# SJ2096POE_USB.net
KiCad netlist of a schematic drawn in Altium Designer
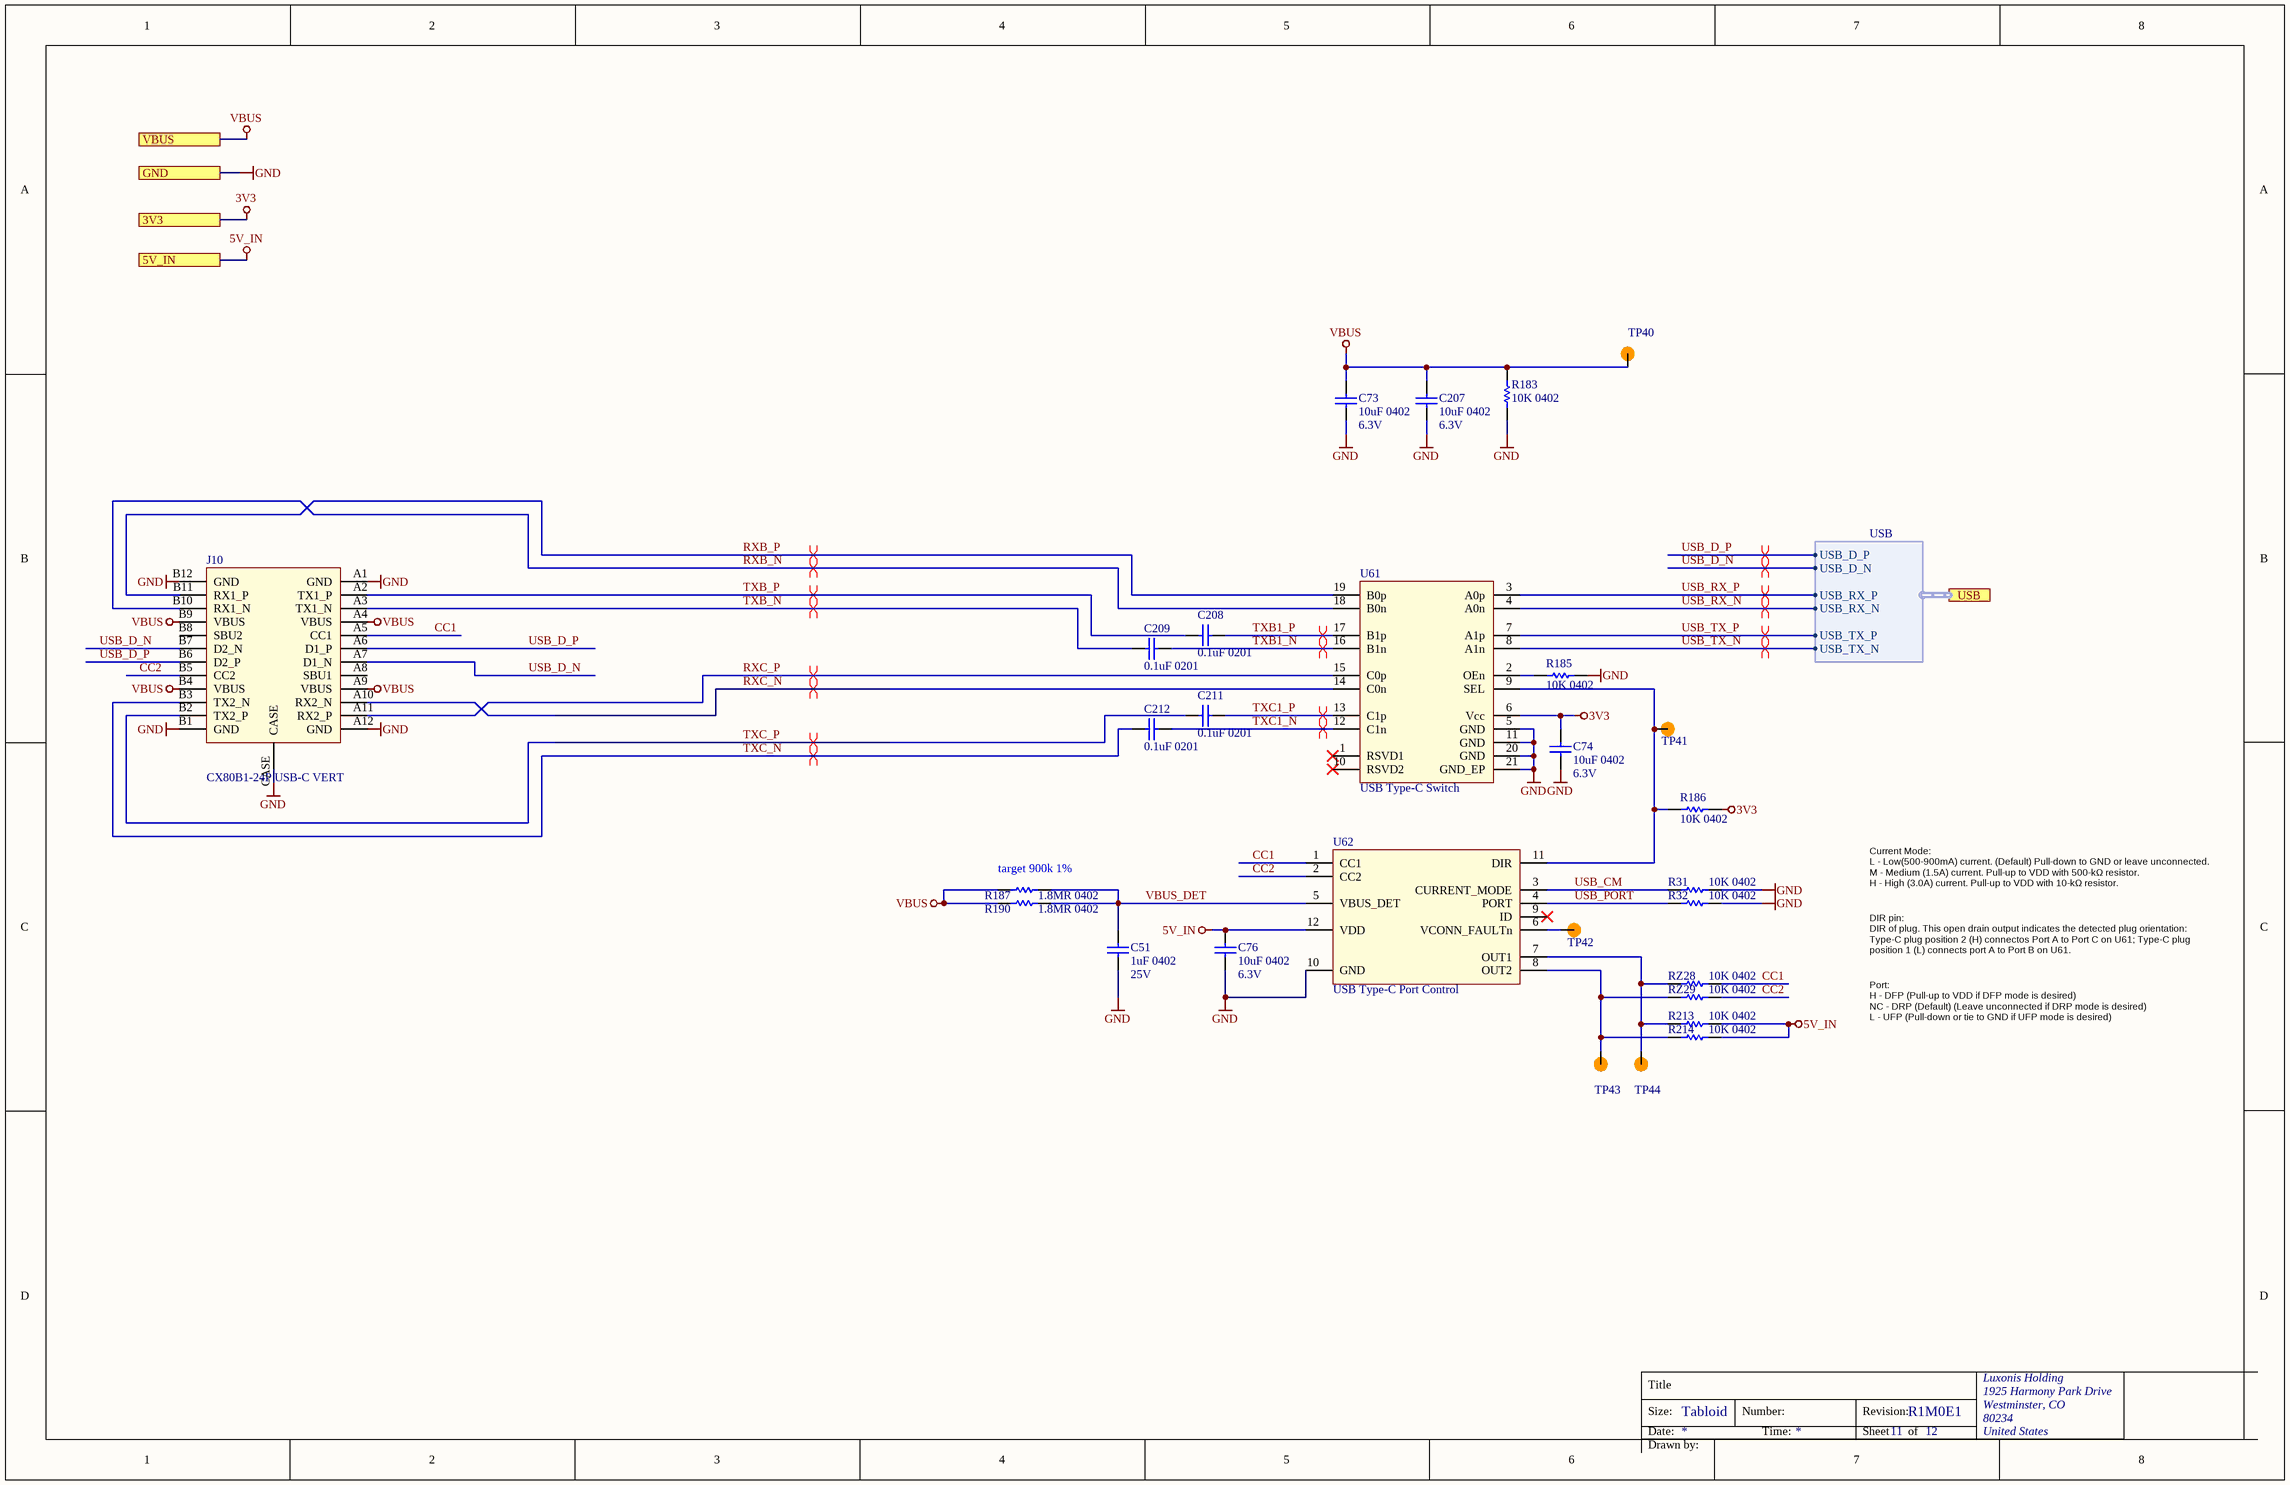
[diagram p0: SJ2096POE_USB.SchDoc]

(export (version "E")
  (design (tool "Eeschema 10.0.6"))
  (components
    (comp (ref "C51")
      (value "1uF 0402")
      (footprint "CAP_Altium_Vault_Generic:CAPC0402(1005)70_N")
      (description "CAP CER 1UF 25V X5R 0402 10%")
      (fields
        (field (name "TOLERANCE") "10%")
        (field (name "VOLTAGE") "25V")
        (field (name "VOLTAGE RATING") "25V")
      )
      (libsource (lib "LuxonisMaster") (part "GRM155R61E105KA12D"))
    )
    (comp (ref "C73")
      (value "10uF 0402")
      (footprint "CAP_Altium_Vault_Generic:CAPC0402(1005)70_N")
      (description "CAP CER 10UF 6.3V X5R 0402 20%")
      (fields (field (name "TOLERANCE") "20%") (field (name "VOLTAGE RATING") "6.3V"))
      (libsource (lib "LuxonisMaster") (part "GRM155R60J106ME15D"))
    )
    (comp (ref "C74")
      (value "10uF 0402")
      (footprint "CAP_Altium_Vault_Generic:CAPC0402(1005)70_N")
      (description "CAP CER 10UF 6.3V X5R 0402 20%")
      (fields (field (name "TOLERANCE") "20%") (field (name "VOLTAGE RATING") "6.3V"))
      (libsource (lib "LuxonisMaster") (part "GRM155R60J106ME15D"))
    )
    (comp (ref "C76")
      (value "10uF 0402")
      (footprint "CAP_Altium_Vault_Generic:CAPC0402(1005)70_N")
      (description "CAP CER 10UF 6.3V X5R 0402 20%")
      (fields (field (name "TOLERANCE") "20%") (field (name "VOLTAGE RATING") "6.3V"))
      (libsource (lib "LuxonisMaster") (part "GRM155R60J106ME15D"))
    )
    (comp (ref "C207")
      (value "10uF 0402")
      (footprint "CAP_Altium_Vault_Generic:CAPC0402(1005)70_N")
      (description "CAP CER 10UF 6.3V X5R 0402 20%")
      (fields (field (name "TOLERANCE") "20%") (field (name "VOLTAGE RATING") "6.3V"))
      (libsource (lib "LuxonisMaster") (part "GRM155R60J106ME15D"))
    )
    (comp (ref "C208")
      (value "0.1uF 0201")
      (footprint "CAP_Altium_Vault_Generic:CAPC0201(0603)33_L")
      (description "CAP CER 0.1UF 10V X5R 0201")
      (fields (field (name "TOLERANCE") "10%") (field (name "VOLTAGE") "10V"))
      (libsource (lib "LuxonisMaster") (part "GRM033R61A104KE15D"))
    )
    (comp (ref "C209")
      (value "0.1uF 0201")
      (footprint "CAP_Altium_Vault_Generic:CAPC0201(0603)33_L")
      (description "CAP CER 0.1UF 10V X5R 0201")
      (fields (field (name "TOLERANCE") "10%") (field (name "VOLTAGE") "10V"))
      (libsource (lib "LuxonisMaster") (part "GRM033R61A104KE15D"))
    )
    (comp (ref "C211")
      (value "0.1uF 0201")
      (footprint "CAP_Altium_Vault_Generic:CAPC0201(0603)33_L")
      (description "CAP CER 0.1UF 10V X5R 0201")
      (fields (field (name "TOLERANCE") "10%") (field (name "VOLTAGE") "10V"))
      (libsource (lib "LuxonisMaster") (part "GRM033R61A104KE15D"))
    )
    (comp (ref "C212")
      (value "0.1uF 0201")
      (footprint "CAP_Altium_Vault_Generic:CAPC0201(0603)33_L")
      (description "CAP CER 0.1UF 10V X5R 0201")
      (fields (field (name "TOLERANCE") "10%") (field (name "VOLTAGE") "10V"))
      (libsource (lib "LuxonisMaster") (part "GRM033R61A104KE15D"))
    )
    (comp (ref "J10")
      (value "CX80B1-24P USB-C VERT")
      (footprint "CX80B1-24P")
      (description "USB - C USB 3.0 (USB 3.1 Gen 1 Superspeed) Male Receptacle Connector 24 Position")
      (fields (field (name "MANUFACTURER") "Hirose") (field (name "MANUFACTURER PART NUMBER") "CX80B1-24P"))
      (libsource (lib "MB2096POE") (part "CX80B1-24P"))
    )
    (comp (ref "R31")
      (value "10K 0402")
      (footprint "RES_Altium_Vault_Generic:RESC0402(1005)_N")
      (fields (field (name "TOLERANCE") "1%"))
      (libsource (lib "LuxonisMaster") (part "RC0402FR-1310KL"))
    )
    (comp (ref "R32")
      (value "10K 0402")
      (footprint "RES_Altium_Vault_Generic:RESC0402(1005)_N")
      (fields (field (name "TOLERANCE") "1%"))
      (libsource (lib "LuxonisMaster") (part "RC0402FR-1310KL"))
    )
    (comp (ref "R183")
      (value "10K 0402")
      (footprint "RES_Altium_Vault_Generic:RESC0402(1005)_N")
      (fields (field (name "TOLERANCE") "1%"))
      (libsource (lib "LuxonisMaster") (part "RC0402FR-1310KL"))
    )
    (comp (ref "R185")
      (value "10K 0402")
      (footprint "RES_Altium_Vault_Generic:RESC0402(1005)_N")
      (fields (field (name "TOLERANCE") "1%"))
      (libsource (lib "LuxonisMaster") (part "RC0402FR-1310KL"))
    )
    (comp (ref "R186")
      (value "10K 0402")
      (footprint "RES_Altium_Vault_Generic:RESC0402(1005)_N")
      (fields (field (name "TOLERANCE") "1%"))
      (libsource (lib "LuxonisMaster") (part "RC0402FR-1310KL"))
    )
    (comp (ref "R187")
      (value "1.8MR 0402")
      (footprint "RES_Altium_Vault_Generic:RESC0402(1005)_N")
      (description "RES SMD 1.8M OHM 1% 1/16W 0402")
      (fields (field (name "TOLERANCE") "1%"))
      (libsource (lib "LuxonisMaster") (part "CRCW04021M80FKED"))
    )
    (comp (ref "R190")
      (value "1.8MR 0402")
      (footprint "RES_Altium_Vault_Generic:RESC0402(1005)_N")
      (description "RES SMD 1.8M OHM 1% 1/16W 0402")
      (fields (field (name "TOLERANCE") "1%"))
      (libsource (lib "LuxonisMaster") (part "CRCW04021M80FKED"))
    )
    (comp (ref "R213")
      (value "10K 0402")
      (footprint "RES_Altium_Vault_Generic:RESC0402(1005)_N")
      (fields (field (name "TOLERANCE") "1%"))
      (libsource (lib "LuxonisMaster") (part "RC0402FR-1310KL"))
    )
    (comp (ref "R214")
      (value "10K 0402")
      (footprint "RES_Altium_Vault_Generic:RESC0402(1005)_N")
      (fields (field (name "TOLERANCE") "1%"))
      (libsource (lib "LuxonisMaster") (part "RC0402FR-1310KL"))
    )
    (comp (ref "RZ28")
      (value "10K 0402")
      (footprint "RES_Altium_Vault_Generic:RESC0402(1005)_N")
      (fields (field (name "TOLERANCE") "1%"))
      (libsource (lib "LuxonisMaster") (part "RC0402FR-1310KL"))
    )
    (comp (ref "RZ29")
      (value "10K 0402")
      (footprint "RES_Altium_Vault_Generic:RESC0402(1005)_N")
      (fields (field (name "TOLERANCE") "1%"))
      (libsource (lib "LuxonisMaster") (part "RC0402FR-1310KL"))
    )
    (comp (ref "TP40")
      (value "TP100_200_NS")
      (footprint "LuxonisMaster:TP100_200_NS")
      (libsource (lib "LuxonisMaster") (part "TEST_POINT"))
    )
    (comp (ref "TP41")
      (value "TP100_200_NS")
      (footprint "LuxonisMaster:TP100_200_NS")
      (libsource (lib "LuxonisMaster") (part "TEST_POINT"))
    )
    (comp (ref "TP42")
      (value "TP100_200_NS")
      (footprint "LuxonisMaster:TP100_200_NS")
      (libsource (lib "LuxonisMaster") (part "TEST_POINT"))
    )
    (comp (ref "TP43")
      (value "TP100_200_NS")
      (footprint "LuxonisMaster:TP100_200_NS")
      (libsource (lib "LuxonisMaster") (part "TEST_POINT"))
    )
    (comp (ref "TP44")
      (value "TP100_200_NS")
      (footprint "LuxonisMaster:TP100_200_NS")
      (libsource (lib "LuxonisMaster") (part "TEST_POINT"))
    )
    (comp (ref "U61")
      (value "USB Type-C Switch")
      (footprint "LuxonisMaster:HD3SS3212RKSR")
      (description "IC MUX 2:1 8 OHM 20VQFN")
      (libsource (lib "LuxonisMaster") (part "HD3SS3212RKSR"))
    )
    (comp (ref "U62")
      (value "USB Type-C Port Control")
      (footprint "LuxonisMaster:TUSB321RWBR")
      (description "IC USB PORT CONTROL TYPE-C 12X2Q")
      (libsource (lib "LuxonisMaster") (part "TUSB321RWBR"))
    )
  )
  (nets
    (net (code "2") (name "/CC1") (class "Default")
      (node (ref "J10") (pin "A5") (pinfunction "CC1_A5") (pintype "passive"))
      (node (ref "RZ28") (pin "2") (pinfunction "2_2") (pintype "passive"))
      (node (ref "U62") (pin "1") (pinfunction "CC1_1") (pintype "passive"))
    )
    (net (code "3") (name "/CC2") (class "Default")
      (node (ref "J10") (pin "B5") (pinfunction "CC2_B5") (pintype "passive"))
      (node (ref "RZ29") (pin "2") (pinfunction "2_2") (pintype "passive"))
      (node (ref "U62") (pin "2") (pinfunction "CC2_2") (pintype "passive"))
    )
    (net (code "4") (name "/RXB_N") (class "Default")
      (node (ref "J10") (pin "B10") (pinfunction "RX1_N_B10") (pintype "passive"))
      (node (ref "U61") (pin "18") (pinfunction "B0n_18") (pintype "passive"))
    )
    (net (code "5") (name "/RXB_P") (class "Default")
      (node (ref "J10") (pin "B11") (pinfunction "RX1_P_B11") (pintype "passive"))
      (node (ref "U61") (pin "19") (pinfunction "B0p_19") (pintype "passive"))
    )
    (net (code "6") (name "/RXC_N") (class "Default")
      (node (ref "J10") (pin "A10") (pinfunction "RX2_N_A10") (pintype "passive"))
      (node (ref "U61") (pin "14") (pinfunction "C0n_14") (pintype "passive"))
    )
    (net (code "7") (name "/RXC_P") (class "Default")
      (node (ref "J10") (pin "A11") (pinfunction "RX2_P_A11") (pintype "passive"))
      (node (ref "U61") (pin "15") (pinfunction "C0p_15") (pintype "passive"))
    )
    (net (code "8") (name "/TXB1_N") (class "Default")
      (node (ref "C209") (pin "2") (pinfunction "2_2") (pintype "passive"))
      (node (ref "U61") (pin "16") (pinfunction "B1n_16") (pintype "passive"))
    )
    (net (code "9") (name "/TXB1_P") (class "Default")
      (node (ref "C208") (pin "2") (pinfunction "2_2") (pintype "passive"))
      (node (ref "U61") (pin "17") (pinfunction "B1p_17") (pintype "passive"))
    )
    (net (code "10") (name "/TXB_N") (class "Default")
      (node (ref "C209") (pin "1") (pinfunction "1_1") (pintype "passive"))
      (node (ref "J10") (pin "A3") (pinfunction "TX1_N_A3") (pintype "passive"))
    )
    (net (code "11") (name "/TXB_P") (class "Default")
      (node (ref "C208") (pin "1") (pinfunction "1_1") (pintype "passive"))
      (node (ref "J10") (pin "A2") (pinfunction "TX1_P_A2") (pintype "passive"))
    )
    (net (code "12") (name "/TXC1_N") (class "Default")
      (node (ref "C212") (pin "2") (pinfunction "2_2") (pintype "passive"))
      (node (ref "U61") (pin "12") (pinfunction "C1n_12") (pintype "passive"))
    )
    (net (code "13") (name "/TXC1_P") (class "Default")
      (node (ref "C211") (pin "2") (pinfunction "2_2") (pintype "passive"))
      (node (ref "U61") (pin "13") (pinfunction "C1p_13") (pintype "passive"))
    )
    (net (code "14") (name "/TXC_N") (class "Default")
      (node (ref "C212") (pin "1") (pinfunction "1_1") (pintype "passive"))
      (node (ref "J10") (pin "B3") (pinfunction "TX2_N_B3") (pintype "passive"))
    )
    (net (code "15") (name "/TXC_P") (class "Default")
      (node (ref "C211") (pin "1") (pinfunction "1_1") (pintype "passive"))
      (node (ref "J10") (pin "B2") (pinfunction "TX2_P_B2") (pintype "passive"))
    )
    (net (code "16") (name "/USB_CM") (class "Default")
      (node (ref "R31") (pin "1") (pinfunction "1_1") (pintype "passive"))
      (node (ref "U62") (pin "3") (pinfunction "CURRENT_MODE_3") (pintype "passive"))
    )
    (net (code "17") (name "/USB_D_N") (class "Default")
      (node (ref "J10") (pin "A7") (pinfunction "D1_N_A7") (pintype "passive"))
      (node (ref "J10") (pin "B7") (pinfunction "D2_N_B7") (pintype "passive"))
    )
    (net (code "18") (name "/USB_D_P") (class "Default")
      (node (ref "J10") (pin "A6") (pinfunction "D1_P_A6") (pintype "passive"))
      (node (ref "J10") (pin "B6") (pinfunction "D2_P_B6") (pintype "passive"))
    )
    (net (code "19") (name "/USB_PORT") (class "Default")
      (node (ref "R32") (pin "1") (pinfunction "1_1") (pintype "passive"))
      (node (ref "U62") (pin "4") (pinfunction "PORT_4") (pintype "passive"))
    )
    (net (code "20") (name "/USB_RX_N") (class "Default")
      (node (ref "U61") (pin "4") (pinfunction "A0n_4") (pintype "passive"))
    )
    (net (code "21") (name "/USB_RX_P") (class "Default")
      (node (ref "U61") (pin "3") (pinfunction "A0p_3") (pintype "passive"))
    )
    (net (code "22") (name "/USB_TX_N") (class "Default")
      (node (ref "U61") (pin "8") (pinfunction "A1n_8") (pintype "passive"))
    )
    (net (code "23") (name "/USB_TX_P") (class "Default")
      (node (ref "U61") (pin "7") (pinfunction "A1p_7") (pintype "passive"))
    )
    (net (code "24") (name "/VBUS_DET") (class "Default")
      (node (ref "C51") (pin "2") (pinfunction "2_2") (pintype "passive"))
      (node (ref "R187") (pin "2") (pinfunction "2_2") (pintype "passive"))
      (node (ref "R190") (pin "2") (pinfunction "2_2") (pintype "passive"))
      (node (ref "U62") (pin "5") (pinfunction "VBUS_DET_5") (pintype "passive"))
    )
    (net (code "26") (name "3V3") (class "Default")
      (node (ref "C74") (pin "2") (pinfunction "2_2") (pintype "passive"))
      (node (ref "R186") (pin "2") (pinfunction "2_2") (pintype "passive"))
      (node (ref "U61") (pin "6") (pinfunction "Vcc_6") (pintype "passive"))
    )
    (net (code "27") (name "5V_IN") (class "Default")
      (node (ref "C76") (pin "2") (pinfunction "2_2") (pintype "passive"))
      (node (ref "R213") (pin "2") (pinfunction "2_2") (pintype "passive"))
      (node (ref "R214") (pin "2") (pinfunction "2_2") (pintype "passive"))
      (node (ref "U62") (pin "12") (pinfunction "VDD_12") (pintype "passive"))
    )
    (net (code "28") (name "GND") (class "Default")
      (node (ref "C207") (pin "1") (pinfunction "1_1") (pintype "passive"))
      (node (ref "C51") (pin "1") (pinfunction "1_1") (pintype "passive"))
      (node (ref "C73") (pin "1") (pinfunction "1_1") (pintype "passive"))
      (node (ref "C74") (pin "1") (pinfunction "1_1") (pintype "passive"))
      (node (ref "C76") (pin "1") (pinfunction "1_1") (pintype "passive"))
      (node (ref "J10") (pin "A1") (pinfunction "GND_A1") (pintype "passive"))
      (node (ref "J10") (pin "A12") (pinfunction "GND_A12") (pintype "passive"))
      (node (ref "J10") (pin "B1") (pinfunction "GND_B1") (pintype "passive"))
      (node (ref "J10") (pin "B12") (pinfunction "GND_B12") (pintype "passive"))
      (node (ref "J10") (pin "CASE") (pinfunction "CASE_CASE") (pintype "passive"))
      (node (ref "R183") (pin "1") (pinfunction "1_1") (pintype "passive"))
      (node (ref "R185") (pin "2") (pinfunction "2_2") (pintype "passive"))
      (node (ref "R31") (pin "2") (pinfunction "2_2") (pintype "passive"))
      (node (ref "R32") (pin "2") (pinfunction "2_2") (pintype "passive"))
      (node (ref "U61") (pin "11") (pinfunction "GND_11") (pintype "passive"))
      (node (ref "U61") (pin "20") (pinfunction "GND_20") (pintype "passive"))
      (node (ref "U61") (pin "21") (pinfunction "GND_EP_21") (pintype "passive"))
      (node (ref "U61") (pin "5") (pinfunction "GND_5") (pintype "passive"))
      (node (ref "U62") (pin "10") (pinfunction "GND_10") (pintype "passive"))
    )
    (net (code "29") (name "Net-(U61-OEn)") (class "Default")
      (node (ref "R185") (pin "1") (pinfunction "1_1") (pintype "passive"))
      (node (ref "U61") (pin "2") (pinfunction "OEn_2") (pintype "passive"))
    )
    (net (code "30") (name "Net-(U61-SEL)") (class "Default")
      (node (ref "R186") (pin "1") (pinfunction "1_1") (pintype "passive"))
      (node (ref "TP41") (pin "1") (pintype "passive"))
      (node (ref "U61") (pin "9") (pinfunction "SEL_9") (pintype "passive"))
      (node (ref "U62") (pin "11") (pinfunction "DIR_11") (pintype "passive"))
    )
    (net (code "31") (name "Net-(U62-OUT1)") (class "Default")
      (node (ref "R213") (pin "1") (pinfunction "1_1") (pintype "passive"))
      (node (ref "RZ28") (pin "1") (pinfunction "1_1") (pintype "passive"))
      (node (ref "TP44") (pin "1") (pintype "passive"))
      (node (ref "U62") (pin "7") (pinfunction "OUT1_7") (pintype "passive"))
    )
    (net (code "32") (name "Net-(U62-OUT2)") (class "Default")
      (node (ref "R214") (pin "1") (pinfunction "1_1") (pintype "passive"))
      (node (ref "RZ29") (pin "1") (pinfunction "1_1") (pintype "passive"))
      (node (ref "TP43") (pin "1") (pintype "passive"))
      (node (ref "U62") (pin "8") (pinfunction "OUT2_8") (pintype "passive"))
    )
    (net (code "33") (name "Net-(U62-VCONN_FAULTn)") (class "Default")
      (node (ref "TP42") (pin "1") (pintype "passive"))
      (node (ref "U62") (pin "6") (pinfunction "VCONN_FAULTn_6") (pintype "passive"))
    )
    (net (code "34") (name "VBUS") (class "Default")
      (node (ref "C207") (pin "2") (pinfunction "2_2") (pintype "passive"))
      (node (ref "C73") (pin "2") (pinfunction "2_2") (pintype "passive"))
      (node (ref "J10") (pin "A4") (pinfunction "VBUS_A4") (pintype "passive"))
      (node (ref "J10") (pin "A9") (pinfunction "VBUS_A9") (pintype "passive"))
      (node (ref "J10") (pin "B4") (pinfunction "VBUS_B4") (pintype "passive"))
      (node (ref "J10") (pin "B9") (pinfunction "VBUS_B9") (pintype "passive"))
      (node (ref "R183") (pin "2") (pinfunction "2_2") (pintype "passive"))
      (node (ref "R187") (pin "1") (pinfunction "1_1") (pintype "passive"))
      (node (ref "R190") (pin "1") (pinfunction "1_1") (pintype "passive"))
      (node (ref "TP40") (pin "1") (pintype "passive"))
    )
    (net (code "35") (name "unconnected-(J10-SBU1-PadA8)") (class "Default")
      (node (ref "J10") (pin "A8") (pinfunction "SBU1_A8") (pintype "passive"))
    )
    (net (code "36") (name "unconnected-(J10-SBU2-PadB8)") (class "Default")
      (node (ref "J10") (pin "B8") (pinfunction "SBU2_B8") (pintype "passive"))
    )
    (net (code "37") (name "unconnected-(U61-RSVD1-Pad1)") (class "Default")
      (node (ref "U61") (pin "1") (pinfunction "RSVD1_1") (pintype "passive+no_connect"))
    )
    (net (code "38") (name "unconnected-(U61-RSVD2-Pad10)") (class "Default")
      (node (ref "U61") (pin "10") (pinfunction "RSVD2_10") (pintype "passive+no_connect"))
    )
    (net (code "39") (name "unconnected-(U62-ID-Pad9)") (class "Default")
      (node (ref "U62") (pin "9") (pinfunction "ID_9") (pintype "passive+no_connect"))
    )
  )
)
